# LED_Array.net
KiCad netlist of a schematic drawn in EAGLE
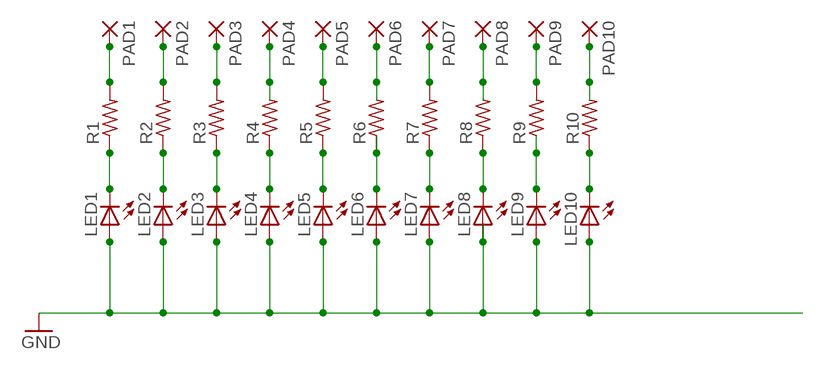
[diagram p0: schematic, sheet 1]

(export (version "E")
  (design (tool "Eeschema 10.0.6"))
  (components
    (comp (ref "LED1")
      (value "LEDSML0805")
      (footprint "eagle-import:SML0805")
      (libsource (lib "eagle-import") (part "LEDSML0805"))
    )
    (comp (ref "LED2")
      (value "LEDSML0805")
      (footprint "eagle-import:SML0805")
      (libsource (lib "eagle-import") (part "LEDSML0805"))
    )
    (comp (ref "LED3")
      (value "LEDSML0805")
      (footprint "eagle-import:SML0805")
      (libsource (lib "eagle-import") (part "LEDSML0805"))
    )
    (comp (ref "LED4")
      (value "LEDSML0805")
      (footprint "eagle-import:SML0805")
      (libsource (lib "eagle-import") (part "LEDSML0805"))
    )
    (comp (ref "LED5")
      (value "LEDSML0805")
      (footprint "eagle-import:SML0805")
      (libsource (lib "eagle-import") (part "LEDSML0805"))
    )
    (comp (ref "LED6")
      (value "LEDSML0805")
      (footprint "eagle-import:SML0805")
      (libsource (lib "eagle-import") (part "LEDSML0805"))
    )
    (comp (ref "LED7")
      (value "LEDSML0805")
      (footprint "eagle-import:SML0805")
      (libsource (lib "eagle-import") (part "LEDSML0805"))
    )
    (comp (ref "LED8")
      (value "LEDSML0805")
      (footprint "eagle-import:SML0805")
      (libsource (lib "eagle-import") (part "LEDSML0805"))
    )
    (comp (ref "LED9")
      (value "LEDSML0805")
      (footprint "eagle-import:SML0805")
      (libsource (lib "eagle-import") (part "LEDSML0805"))
    )
    (comp (ref "LED10")
      (value "LEDSML0805")
      (footprint "eagle-import:SML0805")
      (libsource (lib "eagle-import") (part "LEDSML0805"))
    )
    (comp (ref "PAD1")
      (value "1,6/0,8")
      (footprint "eagle-import:1,6_0,8")
      (libsource (lib "eagle-import") (part "1,6/0,8"))
    )
    (comp (ref "PAD2")
      (value "1,6/0,8")
      (footprint "eagle-import:1,6_0,8")
      (libsource (lib "eagle-import") (part "1,6/0,8"))
    )
    (comp (ref "PAD3")
      (value "1,6/0,8")
      (footprint "eagle-import:1,6_0,8")
      (libsource (lib "eagle-import") (part "1,6/0,8"))
    )
    (comp (ref "PAD4")
      (value "1,6/0,8")
      (footprint "eagle-import:1,6_0,8")
      (libsource (lib "eagle-import") (part "1,6/0,8"))
    )
    (comp (ref "PAD5")
      (value "1,6/0,8")
      (footprint "eagle-import:1,6_0,8")
      (libsource (lib "eagle-import") (part "1,6/0,8"))
    )
    (comp (ref "PAD6")
      (value "1,6/0,8")
      (footprint "eagle-import:1,6_0,8")
      (libsource (lib "eagle-import") (part "1,6/0,8"))
    )
    (comp (ref "PAD7")
      (value "1,6/0,8")
      (footprint "eagle-import:1,6_0,8")
      (libsource (lib "eagle-import") (part "1,6/0,8"))
    )
    (comp (ref "PAD8")
      (value "1,6/0,8")
      (footprint "eagle-import:1,6_0,8")
      (libsource (lib "eagle-import") (part "1,6/0,8"))
    )
    (comp (ref "PAD9")
      (value "1,6/0,8")
      (footprint "eagle-import:1,6_0,8")
      (libsource (lib "eagle-import") (part "1,6/0,8"))
    )
    (comp (ref "PAD10")
      (value "1,6/0,8")
      (footprint "eagle-import:1,6_0,8")
      (libsource (lib "eagle-import") (part "1,6/0,8"))
    )
    (comp (ref "R1")
      (value "R-US_R0805")
      (footprint "eagle-import:R0805")
      (libsource (lib "eagle-import") (part "R-US_R0805"))
    )
    (comp (ref "R2")
      (value "R-US_R0805")
      (footprint "eagle-import:R0805")
      (libsource (lib "eagle-import") (part "R-US_R0805"))
    )
    (comp (ref "R3")
      (value "R-US_R0805")
      (footprint "eagle-import:R0805")
      (libsource (lib "eagle-import") (part "R-US_R0805"))
    )
    (comp (ref "R4")
      (value "R-US_R0805")
      (footprint "eagle-import:R0805")
      (libsource (lib "eagle-import") (part "R-US_R0805"))
    )
    (comp (ref "R5")
      (value "R-US_R0805")
      (footprint "eagle-import:R0805")
      (libsource (lib "eagle-import") (part "R-US_R0805"))
    )
    (comp (ref "R6")
      (value "R-US_R0805")
      (footprint "eagle-import:R0805")
      (libsource (lib "eagle-import") (part "R-US_R0805"))
    )
    (comp (ref "R7")
      (value "R-US_R0805")
      (footprint "eagle-import:R0805")
      (libsource (lib "eagle-import") (part "R-US_R0805"))
    )
    (comp (ref "R8")
      (value "R-US_R0805")
      (footprint "eagle-import:R0805")
      (libsource (lib "eagle-import") (part "R-US_R0805"))
    )
    (comp (ref "R9")
      (value "R-US_R0805")
      (footprint "eagle-import:R0805")
      (libsource (lib "eagle-import") (part "R-US_R0805"))
    )
    (comp (ref "R10")
      (value "R-US_R0805")
      (footprint "eagle-import:R0805")
      (libsource (lib "eagle-import") (part "R-US_R0805"))
    )
  )
  (nets
    (net (code "1") (name "GND") (class "Default")
      (node (ref "LED1") (pin "A") (pinfunction "A_A") (pintype "passive"))
      (node (ref "LED10") (pin "A") (pinfunction "A_A") (pintype "passive"))
      (node (ref "LED2") (pin "A") (pinfunction "A_A") (pintype "passive"))
      (node (ref "LED3") (pin "A") (pinfunction "A_A") (pintype "passive"))
      (node (ref "LED4") (pin "A") (pinfunction "A_A") (pintype "passive"))
      (node (ref "LED5") (pin "A") (pinfunction "A_A") (pintype "passive"))
      (node (ref "LED6") (pin "A") (pinfunction "A_A") (pintype "passive"))
      (node (ref "LED7") (pin "A") (pinfunction "A_A") (pintype "passive"))
      (node (ref "LED8") (pin "A") (pinfunction "A_A") (pintype "passive"))
      (node (ref "LED9") (pin "A") (pinfunction "A_A") (pintype "passive"))
    )
    (net (code "2") (name "Net-(LED1-PadC)") (class "Default")
      (node (ref "LED1") (pin "C") (pinfunction "C_C") (pintype "passive"))
      (node (ref "R1") (pin "1") (pinfunction "1_1") (pintype "passive"))
    )
    (net (code "3") (name "Net-(LED2-PadC)") (class "Default")
      (node (ref "LED2") (pin "C") (pinfunction "C_C") (pintype "passive"))
      (node (ref "R2") (pin "1") (pinfunction "1_1") (pintype "passive"))
    )
    (net (code "4") (name "Net-(LED3-PadC)") (class "Default")
      (node (ref "LED3") (pin "C") (pinfunction "C_C") (pintype "passive"))
      (node (ref "R3") (pin "1") (pinfunction "1_1") (pintype "passive"))
    )
    (net (code "5") (name "Net-(LED4-PadC)") (class "Default")
      (node (ref "LED4") (pin "C") (pinfunction "C_C") (pintype "passive"))
      (node (ref "R4") (pin "1") (pinfunction "1_1") (pintype "passive"))
    )
    (net (code "6") (name "Net-(LED5-PadC)") (class "Default")
      (node (ref "LED5") (pin "C") (pinfunction "C_C") (pintype "passive"))
      (node (ref "R5") (pin "1") (pinfunction "1_1") (pintype "passive"))
    )
    (net (code "7") (name "Net-(LED6-PadC)") (class "Default")
      (node (ref "LED6") (pin "C") (pinfunction "C_C") (pintype "passive"))
      (node (ref "R6") (pin "1") (pinfunction "1_1") (pintype "passive"))
    )
    (net (code "8") (name "Net-(LED7-PadC)") (class "Default")
      (node (ref "LED7") (pin "C") (pinfunction "C_C") (pintype "passive"))
      (node (ref "R7") (pin "1") (pinfunction "1_1") (pintype "passive"))
    )
    (net (code "9") (name "Net-(LED8-PadC)") (class "Default")
      (node (ref "LED8") (pin "C") (pinfunction "C_C") (pintype "passive"))
      (node (ref "R8") (pin "1") (pinfunction "1_1") (pintype "passive"))
    )
    (net (code "10") (name "Net-(LED9-PadC)") (class "Default")
      (node (ref "LED9") (pin "C") (pinfunction "C_C") (pintype "passive"))
      (node (ref "R9") (pin "1") (pinfunction "1_1") (pintype "passive"))
    )
    (net (code "11") (name "Net-(LED10-PadC)") (class "Default")
      (node (ref "LED10") (pin "C") (pinfunction "C_C") (pintype "passive"))
      (node (ref "R10") (pin "1") (pinfunction "1_1") (pintype "passive"))
    )
    (net (code "12") (name "Net-(PAD1-P)") (class "Default")
      (node (ref "PAD1") (pin "1") (pinfunction "P_1") (pintype "passive"))
      (node (ref "R1") (pin "2") (pinfunction "2_2") (pintype "passive"))
    )
    (net (code "13") (name "Net-(PAD2-P)") (class "Default")
      (node (ref "PAD2") (pin "1") (pinfunction "P_1") (pintype "passive"))
      (node (ref "R2") (pin "2") (pinfunction "2_2") (pintype "passive"))
    )
    (net (code "14") (name "Net-(PAD3-P)") (class "Default")
      (node (ref "PAD3") (pin "1") (pinfunction "P_1") (pintype "passive"))
      (node (ref "R3") (pin "2") (pinfunction "2_2") (pintype "passive"))
    )
    (net (code "15") (name "Net-(PAD4-P)") (class "Default")
      (node (ref "PAD4") (pin "1") (pinfunction "P_1") (pintype "passive"))
      (node (ref "R4") (pin "2") (pinfunction "2_2") (pintype "passive"))
    )
    (net (code "16") (name "Net-(PAD5-P)") (class "Default")
      (node (ref "PAD5") (pin "1") (pinfunction "P_1") (pintype "passive"))
      (node (ref "R5") (pin "2") (pinfunction "2_2") (pintype "passive"))
    )
    (net (code "17") (name "Net-(PAD6-P)") (class "Default")
      (node (ref "PAD6") (pin "1") (pinfunction "P_1") (pintype "passive"))
      (node (ref "R6") (pin "2") (pinfunction "2_2") (pintype "passive"))
    )
    (net (code "18") (name "Net-(PAD7-P)") (class "Default")
      (node (ref "PAD7") (pin "1") (pinfunction "P_1") (pintype "passive"))
      (node (ref "R7") (pin "2") (pinfunction "2_2") (pintype "passive"))
    )
    (net (code "19") (name "Net-(PAD8-P)") (class "Default")
      (node (ref "PAD8") (pin "1") (pinfunction "P_1") (pintype "passive"))
      (node (ref "R8") (pin "2") (pinfunction "2_2") (pintype "passive"))
    )
    (net (code "20") (name "Net-(PAD9-P)") (class "Default")
      (node (ref "PAD9") (pin "1") (pinfunction "P_1") (pintype "passive"))
      (node (ref "R9") (pin "2") (pinfunction "2_2") (pintype "passive"))
    )
    (net (code "21") (name "Net-(PAD10-P)") (class "Default")
      (node (ref "PAD10") (pin "1") (pinfunction "P_1") (pintype "passive"))
      (node (ref "R10") (pin "2") (pinfunction "2_2") (pintype "passive"))
    )
  )
)
